# Protect.net
KiCad netlist of a schematic drawn in EAGLE
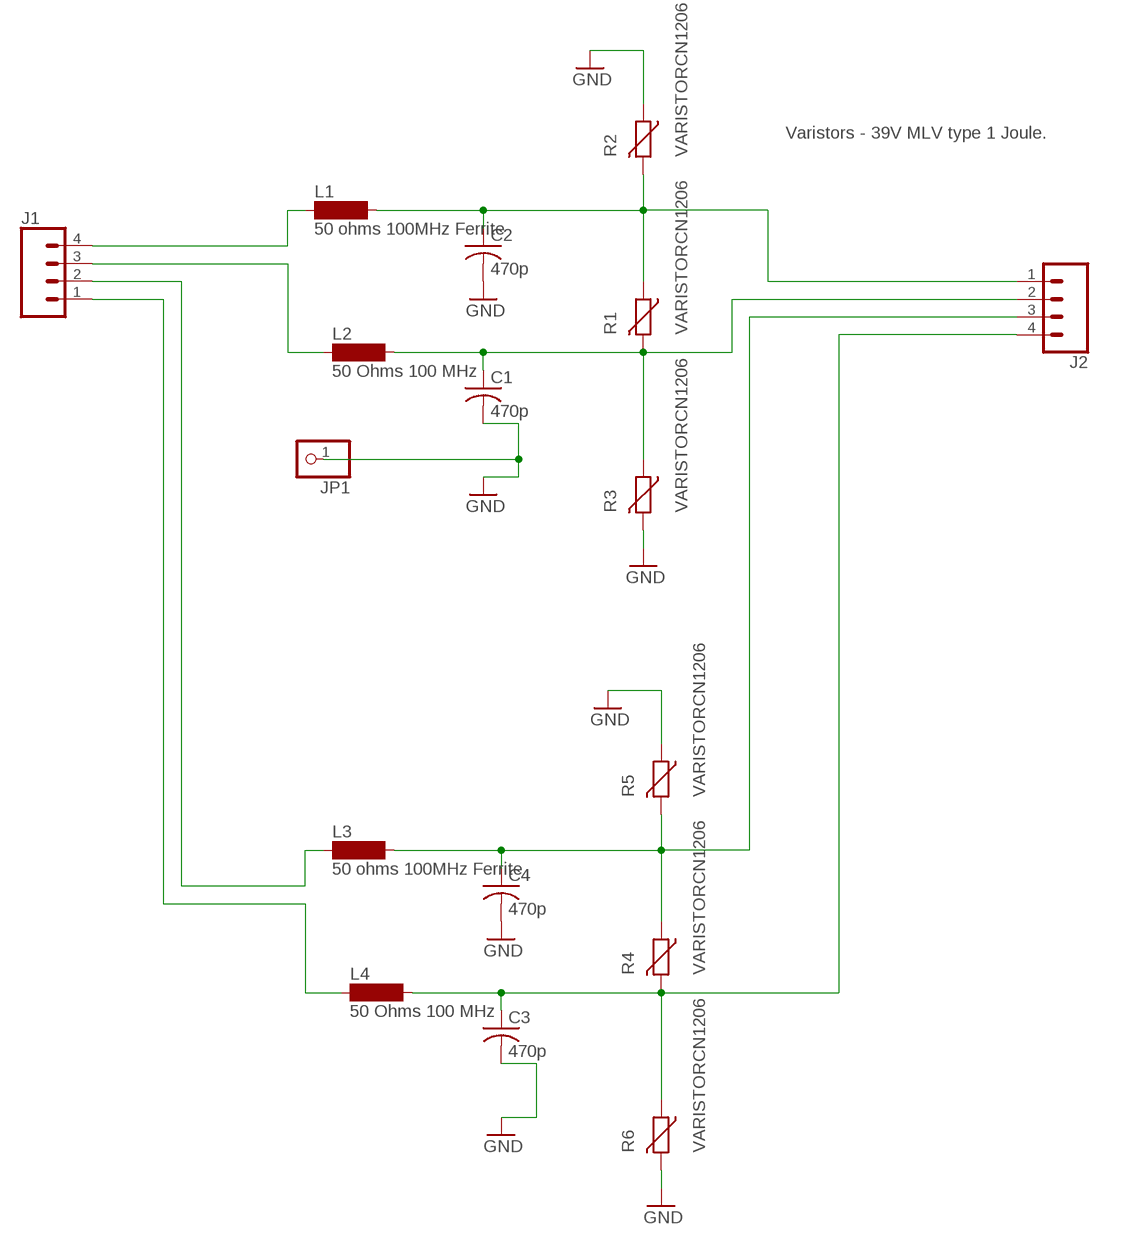
[diagram p0: schematic, sheet 1]

(export (version "E")
  (design (tool "Eeschema 10.0.6"))
  (components
    (comp (ref "C1")
      (value "470p")
      (footprint "eagle-import:C0603K")
      (libsource (lib "eagle-import") (part "C-USC0603K"))
    )
    (comp (ref "C2")
      (value "470p")
      (footprint "eagle-import:C0603K")
      (libsource (lib "eagle-import") (part "C-USC0603K"))
    )
    (comp (ref "C3")
      (value "470p")
      (footprint "eagle-import:C0603K")
      (libsource (lib "eagle-import") (part "C-USC0603K"))
    )
    (comp (ref "C4")
      (value "470p")
      (footprint "eagle-import:C0603K")
      (libsource (lib "eagle-import") (part "C-USC0603K"))
    )
    (comp (ref "J1")
      (value "CONN_04")
      (footprint "eagle-import:1X04")
      (libsource (lib "eagle-import") (part "CONN_04"))
    )
    (comp (ref "J2")
      (value "CONN_04")
      (footprint "eagle-import:1X04")
      (libsource (lib "eagle-import") (part "CONN_04"))
    )
    (comp (ref "JP1")
      (value "PINHD-1X1")
      (footprint "eagle-import:1X01")
      (libsource (lib "eagle-import") (part "PINHD-1X1"))
    )
    (comp (ref "L1")
      (value "50 ohms 100MHz Ferrite")
      (footprint "eagle-import:SM-1206")
      (libsource (lib "eagle-import") (part "SM-1206"))
    )
    (comp (ref "L2")
      (value "50 Ohms 100 MHz")
      (footprint "eagle-import:SM-1206")
      (libsource (lib "eagle-import") (part "SM-1206"))
    )
    (comp (ref "L3")
      (value "50 ohms 100MHz Ferrite")
      (footprint "eagle-import:SM-1206")
      (libsource (lib "eagle-import") (part "SM-1206"))
    )
    (comp (ref "L4")
      (value "50 Ohms 100 MHz")
      (footprint "eagle-import:SM-1206")
      (libsource (lib "eagle-import") (part "SM-1206"))
    )
    (comp (ref "R1")
      (value "VARISTORCN1206")
      (footprint "eagle-import:CT_CN1206")
      (libsource (lib "eagle-import") (part "VARISTORCN1206"))
    )
    (comp (ref "R2")
      (value "VARISTORCN1206")
      (footprint "eagle-import:CT_CN1206")
      (libsource (lib "eagle-import") (part "VARISTORCN1206"))
    )
    (comp (ref "R3")
      (value "VARISTORCN1206")
      (footprint "eagle-import:CT_CN1206")
      (libsource (lib "eagle-import") (part "VARISTORCN1206"))
    )
    (comp (ref "R4")
      (value "VARISTORCN1206")
      (footprint "eagle-import:CT_CN1206")
      (libsource (lib "eagle-import") (part "VARISTORCN1206"))
    )
    (comp (ref "R5")
      (value "VARISTORCN1206")
      (footprint "eagle-import:CT_CN1206")
      (libsource (lib "eagle-import") (part "VARISTORCN1206"))
    )
    (comp (ref "R6")
      (value "VARISTORCN1206")
      (footprint "eagle-import:CT_CN1206")
      (libsource (lib "eagle-import") (part "VARISTORCN1206"))
    )
  )
  (nets
    (net (code "1") (name "GND") (class "Default")
      (node (ref "C1") (pin "2") (pinfunction "2_2") (pintype "passive"))
      (node (ref "C2") (pin "2") (pinfunction "2_2") (pintype "passive"))
      (node (ref "C3") (pin "2") (pinfunction "2_2") (pintype "passive"))
      (node (ref "C4") (pin "2") (pinfunction "2_2") (pintype "passive"))
      (node (ref "JP1") (pin "1") (pinfunction "1_1") (pintype "passive"))
      (node (ref "R2") (pin "1") (pinfunction "1_1") (pintype "passive"))
      (node (ref "R3") (pin "2") (pinfunction "2_2") (pintype "passive"))
      (node (ref "R5") (pin "1") (pinfunction "1_1") (pintype "passive"))
      (node (ref "R6") (pin "2") (pinfunction "2_2") (pintype "passive"))
    )
    (net (code "2") (name "Net-(C1-Pad1)") (class "Default")
      (node (ref "C1") (pin "1") (pinfunction "1_1") (pintype "passive"))
      (node (ref "J2") (pin "2") (pinfunction "2_2") (pintype "passive"))
      (node (ref "L2") (pin "2") (pinfunction "2_2") (pintype "passive"))
      (node (ref "R1") (pin "2") (pinfunction "2_2") (pintype "passive"))
      (node (ref "R3") (pin "1") (pinfunction "1_1") (pintype "passive"))
    )
    (net (code "3") (name "Net-(C2-Pad1)") (class "Default")
      (node (ref "C2") (pin "1") (pinfunction "1_1") (pintype "passive"))
      (node (ref "J2") (pin "1") (pinfunction "1_1") (pintype "passive"))
      (node (ref "L1") (pin "2") (pinfunction "2_2") (pintype "passive"))
      (node (ref "R1") (pin "1") (pinfunction "1_1") (pintype "passive"))
      (node (ref "R2") (pin "2") (pinfunction "2_2") (pintype "passive"))
    )
    (net (code "4") (name "Net-(C3-Pad1)") (class "Default")
      (node (ref "C3") (pin "1") (pinfunction "1_1") (pintype "passive"))
      (node (ref "J2") (pin "4") (pinfunction "4_4") (pintype "passive"))
      (node (ref "L4") (pin "2") (pinfunction "2_2") (pintype "passive"))
      (node (ref "R4") (pin "2") (pinfunction "2_2") (pintype "passive"))
      (node (ref "R6") (pin "1") (pinfunction "1_1") (pintype "passive"))
    )
    (net (code "5") (name "Net-(C4-Pad1)") (class "Default")
      (node (ref "C4") (pin "1") (pinfunction "1_1") (pintype "passive"))
      (node (ref "J2") (pin "3") (pinfunction "3_3") (pintype "passive"))
      (node (ref "L3") (pin "2") (pinfunction "2_2") (pintype "passive"))
      (node (ref "R4") (pin "1") (pinfunction "1_1") (pintype "passive"))
      (node (ref "R5") (pin "2") (pinfunction "2_2") (pintype "passive"))
    )
    (net (code "6") (name "Net-(J1-Pad1)") (class "Default")
      (node (ref "J1") (pin "1") (pinfunction "1_1") (pintype "passive"))
      (node (ref "L4") (pin "1") (pinfunction "1_1") (pintype "passive"))
    )
    (net (code "7") (name "Net-(J1-Pad2)") (class "Default")
      (node (ref "J1") (pin "2") (pinfunction "2_2") (pintype "passive"))
      (node (ref "L3") (pin "1") (pinfunction "1_1") (pintype "passive"))
    )
    (net (code "8") (name "Net-(J1-Pad3)") (class "Default")
      (node (ref "J1") (pin "3") (pinfunction "3_3") (pintype "passive"))
      (node (ref "L2") (pin "1") (pinfunction "1_1") (pintype "passive"))
    )
    (net (code "9") (name "Net-(J1-Pad4)") (class "Default")
      (node (ref "J1") (pin "4") (pinfunction "4_4") (pintype "passive"))
      (node (ref "L1") (pin "1") (pinfunction "1_1") (pintype "passive"))
    )
  )
)
